# LiPoBBSupplyWithCharging.net
KiCad netlist of a schematic drawn in EAGLE
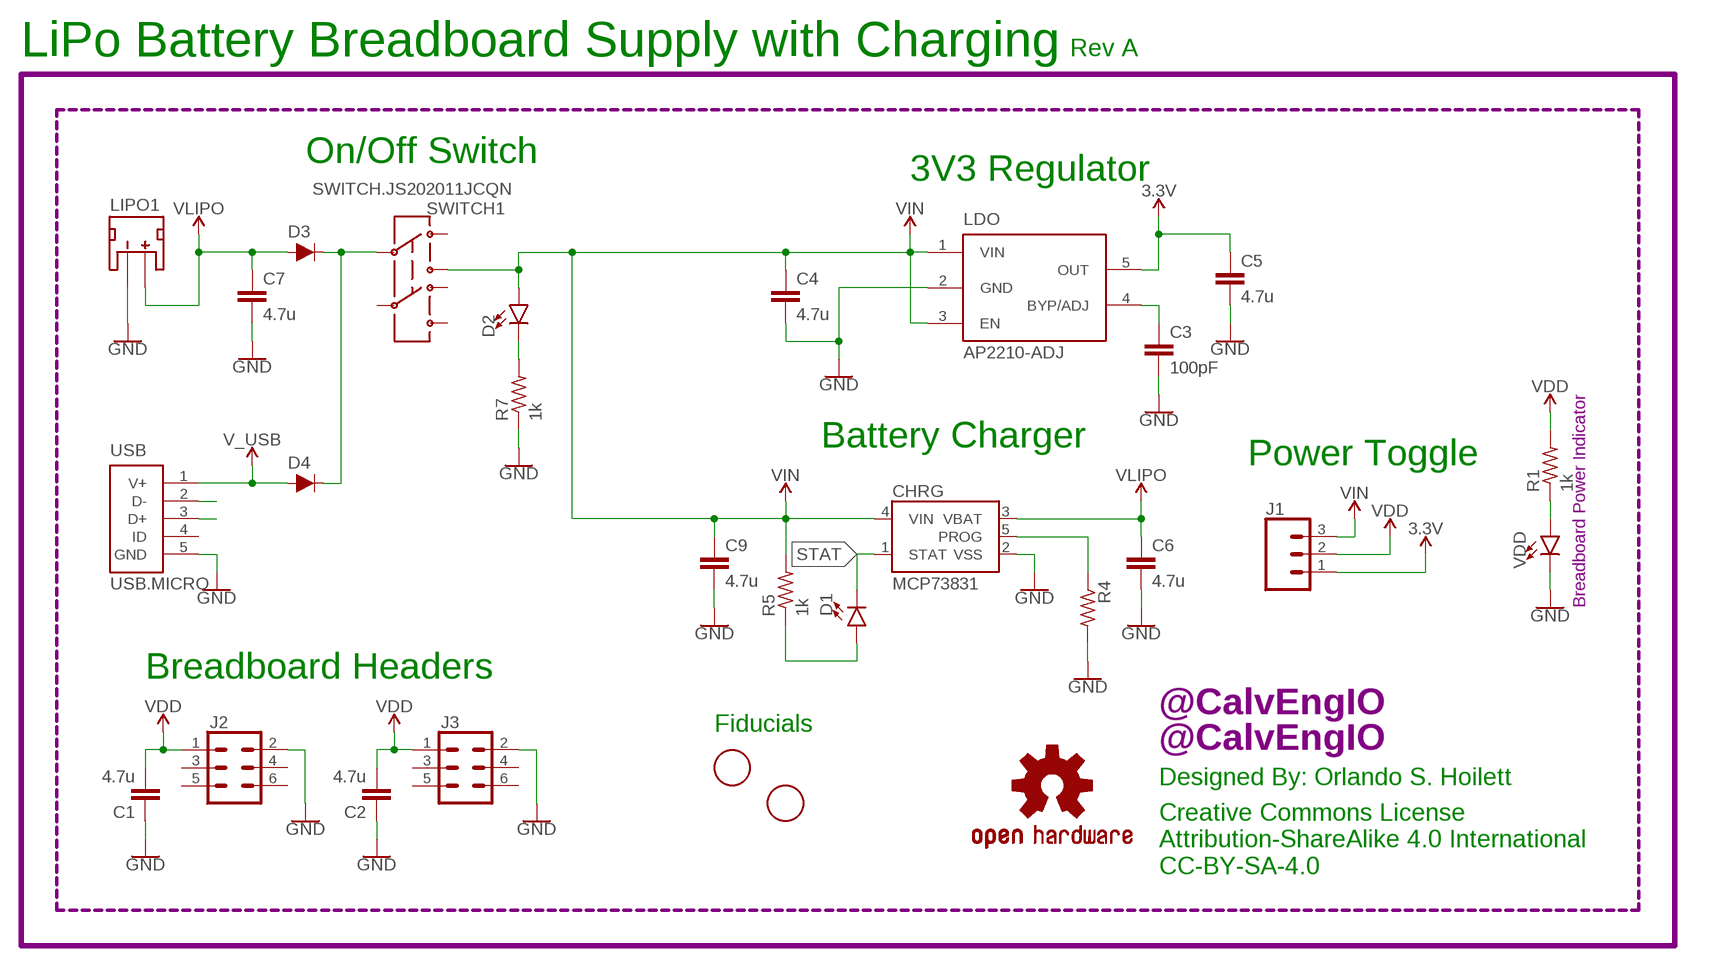
[diagram p0: schematic, sheet 1]

(export (version "E")
  (design (tool "Eeschema 10.0.6"))
  (components
    (comp (ref "C1")
      (value "4.7u")
      (footprint "eagle-import:C0603")
      (libsource (lib "eagle-import") (part "CAPACITOR0603"))
    )
    (comp (ref "C2")
      (value "4.7u")
      (footprint "eagle-import:C0603")
      (libsource (lib "eagle-import") (part "CAPACITOR0603"))
    )
    (comp (ref "C3")
      (value "100pF")
      (footprint "eagle-import:C0402")
      (libsource (lib "eagle-import") (part "C-EUC0402"))
    )
    (comp (ref "C4")
      (value "4.7u")
      (footprint "eagle-import:C0603")
      (libsource (lib "eagle-import") (part "CAPACITOR0603"))
    )
    (comp (ref "C5")
      (value "4.7u")
      (footprint "eagle-import:C0603")
      (libsource (lib "eagle-import") (part "CAPACITOR0603"))
    )
    (comp (ref "C6")
      (value "4.7u")
      (footprint "eagle-import:C0603")
      (libsource (lib "eagle-import") (part "CAPACITOR0603"))
    )
    (comp (ref "C7")
      (value "4.7u")
      (footprint "eagle-import:C0603")
      (libsource (lib "eagle-import") (part "CAPACITOR0603"))
    )
    (comp (ref "C9")
      (value "4.7u")
      (footprint "eagle-import:C0603")
      (libsource (lib "eagle-import") (part "CAPACITOR0603"))
    )
    (comp (ref "CHRG")
      (value "MCP73831")
      (footprint "eagle-import:SOT23-5")
      (libsource (lib "eagle-import") (part "MCP73831"))
    )
    (comp (ref "D1")
      (value "LED0603")
      (footprint "eagle-import:LED-0603")
      (libsource (lib "eagle-import") (part "LED0603"))
    )
    (comp (ref "D2")
      (value "LED0603")
      (footprint "eagle-import:LED-0603")
      (libsource (lib "eagle-import") (part "LED0603"))
    )
    (comp (ref "D3")
      (value "DIODE-BAS16J")
      (footprint "eagle-import:SOD-323")
      (libsource (lib "eagle-import") (part "DIODE-BAS16J"))
    )
    (comp (ref "D4")
      (value "DIODE-BAS16J")
      (footprint "eagle-import:SOD-323")
      (libsource (lib "eagle-import") (part "DIODE-BAS16J"))
    )
    (comp (ref "FD1")
      (value "FIDUCIAL")
      (footprint "eagle-import:FIDUCIAL_1MM")
      (libsource (lib "eagle-import") (part "FIDUCIAL"))
    )
    (comp (ref "FD2")
      (value "FIDUCIAL")
      (footprint "eagle-import:FIDUCIAL_1MM")
      (libsource (lib "eagle-import") (part "FIDUCIAL"))
    )
    (comp (ref "J1")
      (value "CONN_03")
      (footprint "eagle-import:1X03")
      (libsource (lib "eagle-import") (part "CONN_03"))
    )
    (comp (ref "J2")
      (value "CONN_03X22X3_SILK_MALE_PTH")
      (footprint "eagle-import:2X3")
      (libsource (lib "eagle-import") (part "CONN_03X22X3_SILK_MALE_PTH"))
    )
    (comp (ref "J3")
      (value "CONN_03X22X3_SILK_MALE_PTH")
      (footprint "eagle-import:2X3")
      (libsource (lib "eagle-import") (part "CONN_03X22X3_SILK_MALE_PTH"))
    )
    (comp (ref "LDO")
      (value "AP2210-ADJ")
      (footprint "eagle-import:SOT23-5")
      (libsource (lib "eagle-import") (part "AP2210-ADJ"))
    )
    (comp (ref "LIPO1")
      (value "JST_2MM_MALE")
      (footprint "eagle-import:JST-2-SMD")
      (libsource (lib "eagle-import") (part "JST_2MM_MALE"))
    )
    (comp (ref "LOGO1")
      (value "OSHW-LOGOS")
      (footprint "eagle-import:OSHW-LOGO-S")
      (libsource (lib "eagle-import") (part "OSHW-LOGOS"))
    )
    (comp (ref "R1")
      (value "1k")
      (footprint "eagle-import:R0402")
      (libsource (lib "eagle-import") (part "R-US_R0402"))
    )
    (comp (ref "R4")
      (value "RESISTOR0402")
      (footprint "eagle-import:R0402")
      (libsource (lib "eagle-import") (part "RESISTOR0402"))
    )
    (comp (ref "R5")
      (value "1k")
      (footprint "eagle-import:R0402")
      (libsource (lib "eagle-import") (part "RESISTOR0402"))
    )
    (comp (ref "R7")
      (value "1k")
      (footprint "eagle-import:R0402")
      (libsource (lib "eagle-import") (part "RESISTOR0402"))
    )
    (comp (ref "SWITCH1")
      (value "SWITCH.JS202011JCQN")
      (footprint "eagle-import:SWITCH.00")
      (libsource (lib "eagle-import") (part "SWITCH.JS202011JCQN"))
    )
    (comp (ref "U$1")
      (value "HANDLE.1HANDLE.025")
      (footprint "eagle-import:HANDLE.025")
      (libsource (lib "eagle-import") (part "HANDLE.1HANDLE.025"))
    )
    (comp (ref "U$3")
      (value "CALVENGIO_HANDLEHANDLE.1")
      (footprint "eagle-import:CALVENGIO_HANDLE.1")
      (libsource (lib "eagle-import") (part "CALVENGIO_HANDLEHANDLE.1"))
    )
    (comp (ref "USB")
      (value "USB.MICRO")
      (footprint "eagle-import:USB-MICRO-01")
      (libsource (lib "eagle-import") (part "USB.MICRO"))
    )
    (comp (ref "VDD")
      (value "LED0603")
      (footprint "eagle-import:LED-0603")
      (libsource (lib "eagle-import") (part "LED0603"))
    )
  )
  (nets
    (net (code "1") (name "3.3V") (class "Default")
      (node (ref "C5") (pin "1") (pinfunction "1_1") (pintype "passive"))
      (node (ref "J1") (pin "1") (pinfunction "1_1") (pintype "passive"))
      (node (ref "LDO") (pin "5") (pinfunction "OUT_5") (pintype "bidirectional"))
    )
    (net (code "2") (name "GND") (class "Default")
      (node (ref "C1") (pin "1") (pinfunction "1_1") (pintype "passive"))
      (node (ref "C2") (pin "1") (pinfunction "1_1") (pintype "passive"))
      (node (ref "C3") (pin "2") (pinfunction "2_2") (pintype "passive"))
      (node (ref "C4") (pin "2") (pinfunction "2_2") (pintype "passive"))
      (node (ref "C5") (pin "2") (pinfunction "2_2") (pintype "passive"))
      (node (ref "C6") (pin "2") (pinfunction "2_2") (pintype "passive"))
      (node (ref "C7") (pin "2") (pinfunction "2_2") (pintype "passive"))
      (node (ref "C9") (pin "2") (pinfunction "2_2") (pintype "passive"))
      (node (ref "CHRG") (pin "2") (pinfunction "VSS_2") (pintype "power_in"))
      (node (ref "J2") (pin "2") (pinfunction "2_2") (pintype "bidirectional"))
      (node (ref "J3") (pin "2") (pinfunction "2_2") (pintype "bidirectional"))
      (node (ref "LDO") (pin "2") (pinfunction "GND_2") (pintype "bidirectional"))
      (node (ref "LIPO1") (pin "1") (pinfunction "-_1") (pintype "bidirectional"))
      (node (ref "R4") (pin "2") (pinfunction "2_2") (pintype "passive"))
      (node (ref "R7") (pin "1") (pinfunction "1_1") (pintype "passive"))
      (node (ref "USB") (pin "5") (pinfunction "GND_5") (pintype "bidirectional"))
      (node (ref "VDD") (pin "C") (pinfunction "C_C") (pintype "passive"))
    )
    (net (code "3") (name "Net-(CHRG-PROG)") (class "Default")
      (node (ref "CHRG") (pin "5") (pinfunction "PROG_5") (pintype "input"))
      (node (ref "R4") (pin "1") (pinfunction "1_1") (pintype "passive"))
    )
    (net (code "4") (name "Net-(D1-PadA)") (class "Default")
      (node (ref "D1") (pin "A") (pinfunction "A_A") (pintype "passive"))
      (node (ref "R5") (pin "1") (pinfunction "1_1") (pintype "passive"))
    )
    (net (code "5") (name "Net-(D2-PadC)") (class "Default")
      (node (ref "D2") (pin "C") (pinfunction "C_C") (pintype "passive"))
      (node (ref "R7") (pin "2") (pinfunction "2_2") (pintype "passive"))
    )
    (net (code "6") (name "Net-(D3-PadC)") (class "Default")
      (node (ref "D3") (pin "C") (pinfunction "C_C") (pintype "passive"))
      (node (ref "D4") (pin "C") (pinfunction "C_C") (pintype "passive"))
      (node (ref "SWITCH1") (pin "2") (pinfunction "2_2") (pintype "bidirectional"))
    )
    (net (code "7") (name "Net-(LDO-BYP{slash}ADJ)") (class "Default")
      (node (ref "C3") (pin "1") (pinfunction "1_1") (pintype "passive"))
      (node (ref "LDO") (pin "4") (pinfunction "BYP/ADJ_4") (pintype "bidirectional"))
    )
    (net (code "8") (name "Net-(R1-Pad1)") (class "Default")
      (node (ref "R1") (pin "1") (pinfunction "1_1") (pintype "passive"))
      (node (ref "VDD") (pin "A") (pinfunction "A_A") (pintype "passive"))
    )
    (net (code "9") (name "STAT") (class "Default")
      (node (ref "CHRG") (pin "1") (pinfunction "STAT_1") (pintype "output"))
      (node (ref "D1") (pin "C") (pinfunction "C_C") (pintype "passive"))
    )
    (net (code "10") (name "VDD") (class "Default")
      (node (ref "C1") (pin "2") (pinfunction "2_2") (pintype "passive"))
      (node (ref "C2") (pin "2") (pinfunction "2_2") (pintype "passive"))
      (node (ref "J1") (pin "2") (pinfunction "2_2") (pintype "passive"))
      (node (ref "J2") (pin "1") (pinfunction "1_1") (pintype "bidirectional"))
      (node (ref "J3") (pin "1") (pinfunction "1_1") (pintype "bidirectional"))
      (node (ref "R1") (pin "2") (pinfunction "2_2") (pintype "passive"))
    )
    (net (code "11") (name "VIN") (class "Default")
      (node (ref "C4") (pin "1") (pinfunction "1_1") (pintype "passive"))
      (node (ref "C9") (pin "1") (pinfunction "1_1") (pintype "passive"))
      (node (ref "CHRG") (pin "4") (pinfunction "VIN_4") (pintype "power_in"))
      (node (ref "D2") (pin "A") (pinfunction "A_A") (pintype "passive"))
      (node (ref "J1") (pin "3") (pinfunction "3_3") (pintype "passive"))
      (node (ref "LDO") (pin "1") (pinfunction "VIN_1") (pintype "bidirectional"))
      (node (ref "LDO") (pin "3") (pinfunction "EN_3") (pintype "bidirectional"))
      (node (ref "R5") (pin "2") (pinfunction "2_2") (pintype "passive"))
      (node (ref "SWITCH1") (pin "3") (pinfunction "3_3") (pintype "bidirectional"))
    )
    (net (code "12") (name "VLIPO") (class "Default")
      (node (ref "C6") (pin "1") (pinfunction "1_1") (pintype "passive"))
      (node (ref "C7") (pin "1") (pinfunction "1_1") (pintype "passive"))
      (node (ref "CHRG") (pin "3") (pinfunction "VBAT_3") (pintype "power_in"))
      (node (ref "D3") (pin "A") (pinfunction "A_A") (pintype "passive"))
      (node (ref "LIPO1") (pin "2") (pinfunction "+_2") (pintype "bidirectional"))
    )
    (net (code "13") (name "V_USB") (class "Default")
      (node (ref "D4") (pin "A") (pinfunction "A_A") (pintype "passive"))
      (node (ref "USB") (pin "1") (pinfunction "V+_1") (pintype "bidirectional"))
    )
    (net (code "14") (name "unconnected-(J2-Pad3)") (class "Default")
      (node (ref "J2") (pin "3") (pinfunction "3_3") (pintype "bidirectional"))
    )
    (net (code "15") (name "unconnected-(J2-Pad4)") (class "Default")
      (node (ref "J2") (pin "4") (pinfunction "4_4") (pintype "bidirectional"))
    )
    (net (code "16") (name "unconnected-(J2-Pad5)") (class "Default")
      (node (ref "J2") (pin "5") (pinfunction "5_5") (pintype "bidirectional"))
    )
    (net (code "17") (name "unconnected-(J2-Pad6)") (class "Default")
      (node (ref "J2") (pin "6") (pinfunction "6_6") (pintype "bidirectional"))
    )
    (net (code "18") (name "unconnected-(J3-Pad3)") (class "Default")
      (node (ref "J3") (pin "3") (pinfunction "3_3") (pintype "bidirectional"))
    )
    (net (code "19") (name "unconnected-(J3-Pad4)") (class "Default")
      (node (ref "J3") (pin "4") (pinfunction "4_4") (pintype "bidirectional"))
    )
    (net (code "20") (name "unconnected-(J3-Pad5)") (class "Default")
      (node (ref "J3") (pin "5") (pinfunction "5_5") (pintype "bidirectional"))
    )
    (net (code "21") (name "unconnected-(J3-Pad6)") (class "Default")
      (node (ref "J3") (pin "6") (pinfunction "6_6") (pintype "bidirectional"))
    )
    (net (code "22") (name "unconnected-(LIPO1-PAD1-PadNC1)") (class "Default")
      (node (ref "LIPO1") (pin "NC1") (pinfunction "PAD1_NC1") (pintype "bidirectional"))
    )
    (net (code "23") (name "unconnected-(LIPO1-PAD2-PadNC2)") (class "Default")
      (node (ref "LIPO1") (pin "NC2") (pinfunction "PAD2_NC2") (pintype "bidirectional"))
    )
    (net (code "24") (name "unconnected-(SWITCH1-Pad1)") (class "Default")
      (node (ref "SWITCH1") (pin "1") (pinfunction "1_1") (pintype "bidirectional"))
    )
    (net (code "25") (name "unconnected-(SWITCH1-Pad5)") (class "Default")
      (node (ref "SWITCH1") (pin "5") (pinfunction "5_5") (pintype "bidirectional"))
    )
    (net (code "26") (name "unconnected-(SWITCH1-Pad6)") (class "Default")
      (node (ref "SWITCH1") (pin "6") (pinfunction "6_6") (pintype "bidirectional"))
    )
    (net (code "27") (name "unconnected-(SWITCH1-Pad7)") (class "Default")
      (node (ref "SWITCH1") (pin "7") (pinfunction "7_7") (pintype "bidirectional"))
    )
    (net (code "28") (name "unconnected-(USB-D+-Pad3)") (class "Default")
      (node (ref "USB") (pin "3") (pinfunction "D+_3") (pintype "bidirectional"))
    )
    (net (code "29") (name "unconnected-(USB-D--Pad2)") (class "Default")
      (node (ref "USB") (pin "2") (pinfunction "D-_2") (pintype "bidirectional"))
    )
    (net (code "30") (name "unconnected-(USB-ID-Pad4)") (class "Default")
      (node (ref "USB") (pin "4") (pinfunction "ID_4") (pintype "bidirectional"))
    )
  )
)
